# Water_Smart_SchematicV2.net
KiCad netlist of a schematic drawn in Altium Designer
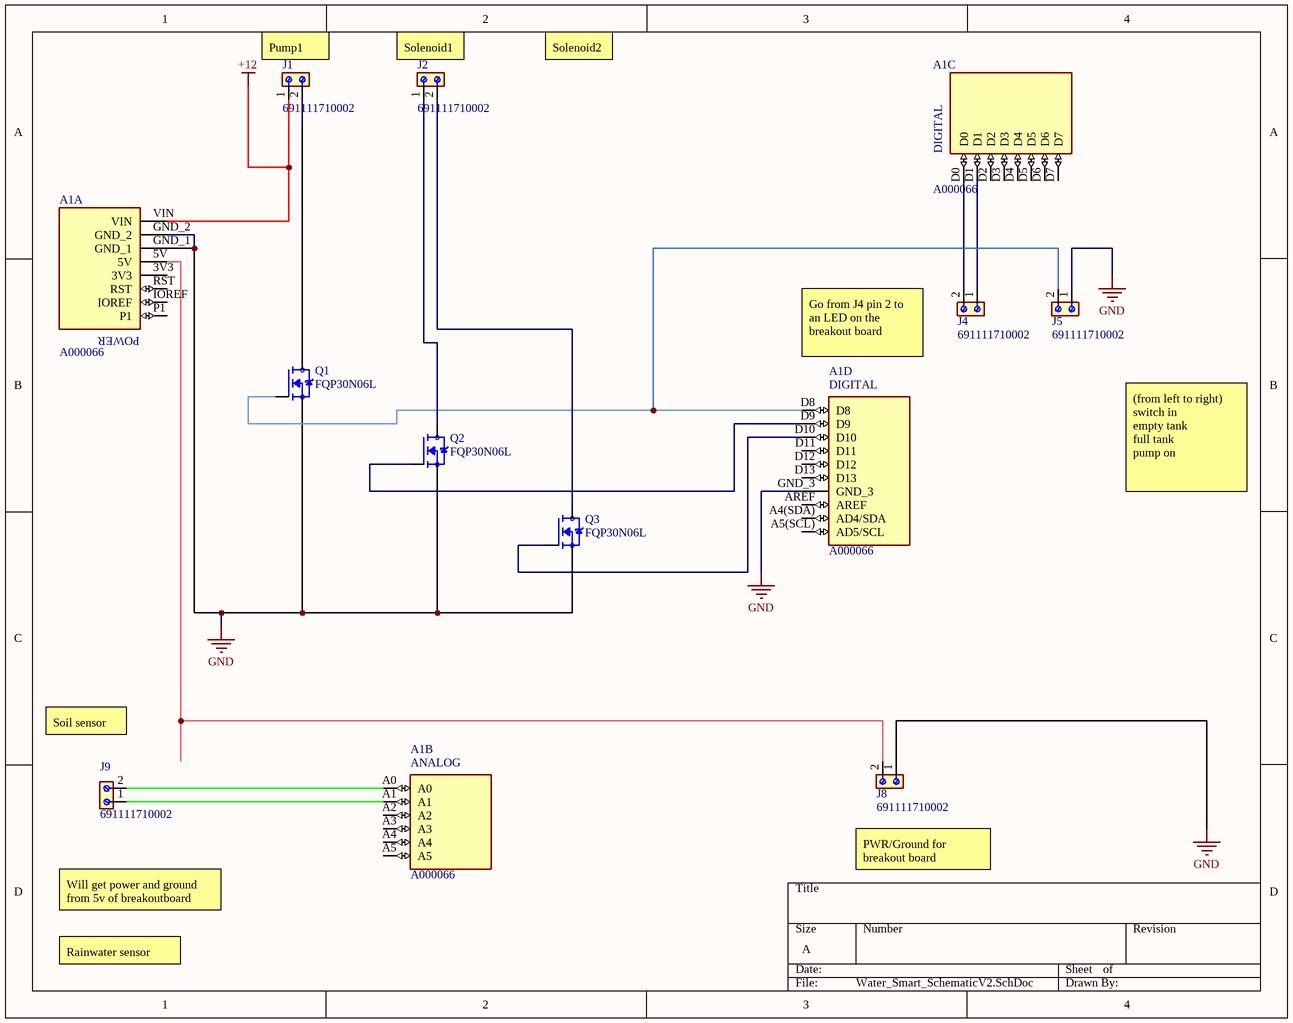
[diagram p0: Water_Smart_SchematicV2.SchDoc]

(export (version "E")
  (design (tool "Eeschema 10.0.6"))
  (components
    (comp (ref "A1")
      (value "A000066")
      (footprint "ARDUINO_A000066")
      (description "Microcontroller board based on the ATmega328P.")
      (fields (field (name "MF") "Arduino") (field (name "MP") "Arduino Uno Rev3"))
      (libsource (lib "") (part "A000066_1"))
    )
    (comp (ref "J1")
      (value "691111710002")
      (footprint "691111710002")
      (description "2 Position Wire to Board Terminal Block Horizontal with Board 0.197 (5.00mm) Through Hole")
      (fields (field (name "MF") "Wurth Electronics"))
      (libsource (lib "691111710002 (Wire Terminal)") (part "691111710002"))
    )
    (comp (ref "J2")
      (value "691111710002")
      (footprint "691111710002")
      (description "2 Position Wire to Board Terminal Block Horizontal with Board 0.197 (5.00mm) Through Hole")
      (fields (field (name "MF") "Wurth Electronics"))
      (libsource (lib "691111710002 (Wire Terminal)") (part "691111710002"))
    )
    (comp (ref "J4")
      (value "691111710002")
      (footprint "691111710002")
      (description "2 Position Wire to Board Terminal Block Horizontal with Board 0.197 (5.00mm) Through Hole")
      (fields (field (name "MF") "Wurth Electronics"))
      (libsource (lib "") (part "691111710002_1"))
    )
    (comp (ref "J5")
      (value "691111710002")
      (footprint "691111710002")
      (description "2 Position Wire to Board Terminal Block Horizontal with Board 0.197 (5.00mm) Through Hole")
      (fields (field (name "MF") "Wurth Electronics"))
      (libsource (lib "") (part "691111710002_1"))
    )
    (comp (ref "J8")
      (value "691111710002")
      (footprint "691111710002")
      (description "2 Position Wire to Board Terminal Block Horizontal with Board 0.197 (5.00mm) Through Hole")
      (fields (field (name "MF") "Wurth Electronics"))
      (libsource (lib "") (part "691111710002_1"))
    )
    (comp (ref "J9")
      (value "691111710002")
      (footprint "691111710002")
      (description "2 Position Wire to Board Terminal Block Horizontal with Board 0.197 (5.00mm) Through Hole")
      (fields (field (name "MF") "Wurth Electronics"))
      (libsource (lib "") (part "691111710002_2"))
    )
    (comp (ref "Q1")
      (value "FQP30N06L")
      (footprint "TO220V")
      (description "N-Channel 60V 32A _Tc_ 79W _Tc_ Through Hole TO-220-3")
      (fields (field (name "MF") "ON Semiconductor"))
      (libsource (lib "FQP30N06L") (part "FQP30N06L"))
    )
    (comp (ref "Q2")
      (value "FQP30N06L")
      (footprint "TO220V")
      (description "N-Channel 60V 32A _Tc_ 79W _Tc_ Through Hole TO-220-3")
      (fields (field (name "MF") "ON Semiconductor"))
      (libsource (lib "FQP30N06L") (part "FQP30N06L"))
    )
    (comp (ref "Q3")
      (value "FQP30N06L")
      (footprint "TO220V")
      (description "N-Channel 60V 32A _Tc_ 79W _Tc_ Through Hole TO-220-3")
      (fields (field (name "MF") "ON Semiconductor"))
      (libsource (lib "FQP30N06L") (part "FQP30N06L"))
    )
  )
  (nets
    (net (code "1") (name "+12") (class "Default")
      (node (ref "A1") (pin "VIN") (pinfunction "VIN_VIN") (pintype "power_in"))
      (node (ref "J1") (pin "1") (pinfunction "1_1") (pintype "passive"))
    )
    (net (code "2") (name "GND") (class "Default")
      (node (ref "A1") (pin "GND_1") (pinfunction "GND_1_GND_1") (pintype "power_in"))
      (node (ref "A1") (pin "GND_2") (pinfunction "GND_2_GND_2") (pintype "power_in"))
      (node (ref "A1") (pin "GND_3") (pinfunction "GND_3_GND_3") (pintype "power_in"))
      (node (ref "J5") (pin "1") (pinfunction "1_1") (pintype "passive"))
      (node (ref "J8") (pin "1") (pinfunction "1_1") (pintype "passive"))
      (node (ref "Q1") (pin "3") (pinfunction "S_3") (pintype "passive"))
      (node (ref "Q2") (pin "3") (pinfunction "S_3") (pintype "passive"))
      (node (ref "Q3") (pin "3") (pinfunction "S_3") (pintype "passive"))
    )
    (net (code "3") (name "Net-(A1-Pad5V)") (class "Default")
      (node (ref "A1") (pin "5V") (pinfunction "5V_5V") (pintype "power_in"))
      (node (ref "J8") (pin "2") (pinfunction "2_2") (pintype "passive"))
    )
    (net (code "4") (name "Net-(A1-PadA0)") (class "Default")
      (node (ref "A1") (pin "A0") (pinfunction "A0_A0") (pintype "bidirectional"))
      (node (ref "J9") (pin "2") (pinfunction "2_2") (pintype "passive"))
    )
    (net (code "5") (name "Net-(A1-PadA1)") (class "Default")
      (node (ref "A1") (pin "A1") (pinfunction "A1_A1") (pintype "bidirectional"))
      (node (ref "J9") (pin "1") (pinfunction "1_1") (pintype "passive"))
    )
    (net (code "6") (name "Net-(A1-PadD0)") (class "Default")
      (node (ref "A1") (pin "D0") (pinfunction "D0_D0") (pintype "bidirectional"))
      (node (ref "J4") (pin "2") (pinfunction "2_2") (pintype "passive"))
    )
    (net (code "7") (name "Net-(A1-PadD1)") (class "Default")
      (node (ref "A1") (pin "D1") (pinfunction "D1_D1") (pintype "bidirectional"))
      (node (ref "J4") (pin "1") (pinfunction "1_1") (pintype "passive"))
    )
    (net (code "8") (name "Net-(Q1-D)") (class "Default")
      (node (ref "J1") (pin "2") (pinfunction "2_2") (pintype "passive"))
      (node (ref "Q1") (pin "2") (pinfunction "D_2") (pintype "passive"))
    )
    (net (code "9") (name "Net-(Q1-G)") (class "Default")
      (node (ref "A1") (pin "D8") (pinfunction "D8_D8") (pintype "bidirectional"))
      (node (ref "J5") (pin "2") (pinfunction "2_2") (pintype "passive"))
      (node (ref "Q1") (pin "1") (pinfunction "G_1") (pintype "passive"))
    )
    (net (code "10") (name "Net-(Q2-D)") (class "Default")
      (node (ref "J2") (pin "1") (pinfunction "1_1") (pintype "passive"))
      (node (ref "Q2") (pin "2") (pinfunction "D_2") (pintype "passive"))
    )
    (net (code "11") (name "Net-(Q2-G)") (class "Default")
      (node (ref "A1") (pin "D9") (pinfunction "D9_D9") (pintype "bidirectional"))
      (node (ref "Q2") (pin "1") (pinfunction "G_1") (pintype "passive"))
    )
    (net (code "12") (name "Net-(Q3-D)") (class "Default")
      (node (ref "J2") (pin "2") (pinfunction "2_2") (pintype "passive"))
      (node (ref "Q3") (pin "2") (pinfunction "D_2") (pintype "passive"))
    )
    (net (code "13") (name "Net-(Q3-G)") (class "Default")
      (node (ref "A1") (pin "D10") (pinfunction "D10_D10") (pintype "bidirectional"))
      (node (ref "Q3") (pin "1") (pinfunction "G_1") (pintype "passive"))
    )
    (net (code "14") (name "unconnected-(A1-Pad3V3)") (class "Default")
      (node (ref "A1") (pin "3V3") (pinfunction "3V3_3V3") (pintype "power_in"))
    )
    (net (code "15") (name "unconnected-(A1-PadA2)") (class "Default")
      (node (ref "A1") (pin "A2") (pinfunction "A2_A2") (pintype "bidirectional"))
    )
    (net (code "16") (name "unconnected-(A1-PadA3)") (class "Default")
      (node (ref "A1") (pin "A3") (pinfunction "A3_A3") (pintype "bidirectional"))
    )
    (net (code "17") (name "unconnected-(A1-PadA4)") (class "Default")
      (node (ref "A1") (pin "A4") (pinfunction "A4_A4") (pintype "bidirectional"))
    )
    (net (code "18") (name "unconnected-(A1-PadA5)") (class "Default")
      (node (ref "A1") (pin "A5") (pinfunction "A5_A5") (pintype "bidirectional"))
    )
    (net (code "19") (name "unconnected-(A1-PadAREF)") (class "Default")
      (node (ref "A1") (pin "AREF") (pinfunction "AREF_AREF") (pintype "bidirectional"))
    )
    (net (code "20") (name "unconnected-(A1-PadD2)") (class "Default")
      (node (ref "A1") (pin "D2") (pinfunction "D2_D2") (pintype "bidirectional"))
    )
    (net (code "21") (name "unconnected-(A1-PadD3)") (class "Default")
      (node (ref "A1") (pin "D3") (pinfunction "D3_D3") (pintype "bidirectional"))
    )
    (net (code "22") (name "unconnected-(A1-PadD4)") (class "Default")
      (node (ref "A1") (pin "D4") (pinfunction "D4_D4") (pintype "bidirectional"))
    )
    (net (code "23") (name "unconnected-(A1-PadD5)") (class "Default")
      (node (ref "A1") (pin "D5") (pinfunction "D5_D5") (pintype "bidirectional"))
    )
    (net (code "24") (name "unconnected-(A1-PadD6)") (class "Default")
      (node (ref "A1") (pin "D6") (pinfunction "D6_D6") (pintype "bidirectional"))
    )
    (net (code "25") (name "unconnected-(A1-PadD7)") (class "Default")
      (node (ref "A1") (pin "D7") (pinfunction "D7_D7") (pintype "bidirectional"))
    )
    (net (code "26") (name "unconnected-(A1-PadD11)") (class "Default")
      (node (ref "A1") (pin "D11") (pinfunction "D11_D11") (pintype "bidirectional"))
    )
    (net (code "27") (name "unconnected-(A1-PadD12)") (class "Default")
      (node (ref "A1") (pin "D12") (pinfunction "D12_D12") (pintype "bidirectional"))
    )
    (net (code "28") (name "unconnected-(A1-PadD13)") (class "Default")
      (node (ref "A1") (pin "D13") (pinfunction "D13_D13") (pintype "bidirectional"))
    )
    (net (code "29") (name "unconnected-(A1-PadIOREF)") (class "Default")
      (node (ref "A1") (pin "IOREF") (pinfunction "IOREF_IOREF") (pintype "bidirectional"))
    )
    (net (code "30") (name "unconnected-(A1-PadP1)") (class "Default")
      (node (ref "A1") (pin "P1") (pinfunction "P1_P1") (pintype "bidirectional"))
    )
    (net (code "31") (name "unconnected-(A1-PadRST)") (class "Default")
      (node (ref "A1") (pin "RST") (pinfunction "RST_RST") (pintype "bidirectional"))
    )
    (net (code "32") (name "unconnected-(A1D-AD4{slash}SDA-PadA4(SDA))") (class "Default")
      (node (ref "A1") (pin "A4(SDA)") (pinfunction "AD4/SDA_A4(SDA)") (pintype "bidirectional"))
    )
    (net (code "33") (name "unconnected-(A1D-AD5{slash}SCL-PadA5(SCL))") (class "Default")
      (node (ref "A1") (pin "A5(SCL)") (pinfunction "AD5/SCL_A5(SCL)") (pintype "bidirectional"))
    )
  )
)
